# VoltageControl_V1p1.net
KiCad netlist of a schematic drawn in EAGLE
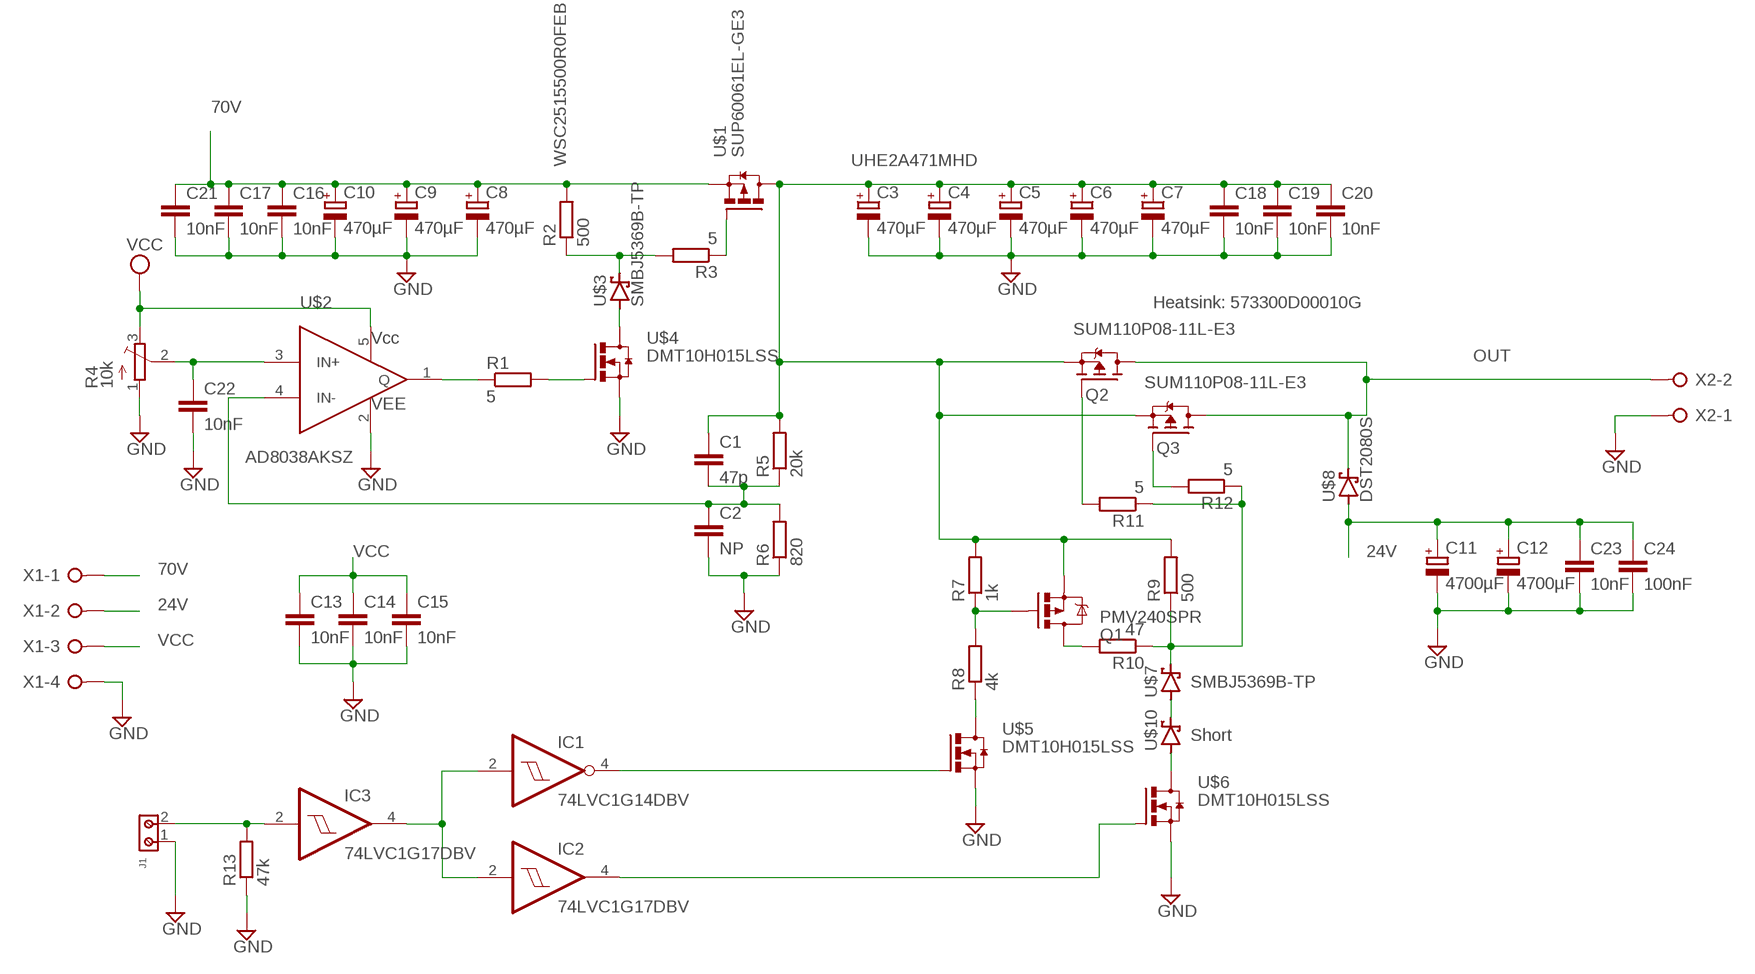
[diagram p0: schematic, sheet 1]

(export (version "E")
  (design (tool "Eeschema 10.0.6"))
  (components
    (comp (ref "C1")
      (value "47p")
      (footprint "eagle-import:C0805")
      (libsource (lib "eagle-import") (part "C-EUC0805"))
    )
    (comp (ref "C2")
      (value "NP")
      (footprint "eagle-import:C0805")
      (libsource (lib "eagle-import") (part "C-EUC0805"))
    )
    (comp (ref "C3")
      (value "470µF")
      (footprint "eagle-import:E7,5-16")
      (libsource (lib "eagle-import") (part "CPOL-EUE7.5-16"))
    )
    (comp (ref "C4")
      (value "470µF")
      (footprint "eagle-import:E7,5-16")
      (libsource (lib "eagle-import") (part "CPOL-EUE7.5-16"))
    )
    (comp (ref "C5")
      (value "470µF")
      (footprint "eagle-import:E7,5-16")
      (libsource (lib "eagle-import") (part "CPOL-EUE7.5-16"))
    )
    (comp (ref "C6")
      (value "470µF")
      (footprint "eagle-import:E7,5-16")
      (libsource (lib "eagle-import") (part "CPOL-EUE7.5-16"))
    )
    (comp (ref "C7")
      (value "470µF")
      (footprint "eagle-import:E7,5-16")
      (libsource (lib "eagle-import") (part "CPOL-EUE7.5-16"))
    )
    (comp (ref "C8")
      (value "470µF")
      (footprint "eagle-import:E7,5-16")
      (libsource (lib "eagle-import") (part "CPOL-EUE7.5-16"))
    )
    (comp (ref "C9")
      (value "470µF")
      (footprint "eagle-import:E7,5-16")
      (libsource (lib "eagle-import") (part "CPOL-EUE7.5-16"))
    )
    (comp (ref "C10")
      (value "470µF")
      (footprint "eagle-import:E7,5-16")
      (libsource (lib "eagle-import") (part "CPOL-EUE7.5-16"))
    )
    (comp (ref "C11")
      (value "4700µF")
      (footprint "eagle-import:E7,5-18")
      (libsource (lib "eagle-import") (part "CPOL-EUE7.5-18"))
    )
    (comp (ref "C12")
      (value "4700µF")
      (footprint "eagle-import:E7,5-18")
      (libsource (lib "eagle-import") (part "CPOL-EUE7.5-18"))
    )
    (comp (ref "C13")
      (value "10nF")
      (footprint "eagle-import:C0805")
      (libsource (lib "eagle-import") (part "C-EUC0805"))
    )
    (comp (ref "C14")
      (value "10nF")
      (footprint "eagle-import:C0805")
      (libsource (lib "eagle-import") (part "C-EUC0805"))
    )
    (comp (ref "C15")
      (value "10nF")
      (footprint "eagle-import:C0805")
      (libsource (lib "eagle-import") (part "C-EUC0805"))
    )
    (comp (ref "C16")
      (value "10nF")
      (footprint "eagle-import:C0805")
      (libsource (lib "eagle-import") (part "C-EUC0805"))
    )
    (comp (ref "C17")
      (value "10nF")
      (footprint "eagle-import:C0805")
      (libsource (lib "eagle-import") (part "C-EUC0805"))
    )
    (comp (ref "C18")
      (value "10nF")
      (footprint "eagle-import:C0805")
      (libsource (lib "eagle-import") (part "C-EUC0805"))
    )
    (comp (ref "C19")
      (value "10nF")
      (footprint "eagle-import:C0805")
      (libsource (lib "eagle-import") (part "C-EUC0805"))
    )
    (comp (ref "C20")
      (value "10nF")
      (footprint "eagle-import:C0805")
      (libsource (lib "eagle-import") (part "C-EUC0805"))
    )
    (comp (ref "C21")
      (value "10nF")
      (footprint "eagle-import:C0805")
      (libsource (lib "eagle-import") (part "C-EUC0805"))
    )
    (comp (ref "C22")
      (value "10nF")
      (footprint "eagle-import:C0805")
      (libsource (lib "eagle-import") (part "C-EUC0805"))
    )
    (comp (ref "C23")
      (value "10nF")
      (footprint "eagle-import:C1206")
      (libsource (lib "eagle-import") (part "C-EUC1206"))
    )
    (comp (ref "C24")
      (value "100nF")
      (footprint "eagle-import:C1206")
      (libsource (lib "eagle-import") (part "C-EUC1206"))
    )
    (comp (ref "IC1")
      (value "74LVC1G14DBV")
      (footprint "eagle-import:SOT23-5")
      (libsource (lib "eagle-import") (part "741G14DBVLVC"))
    )
    (comp (ref "IC2")
      (value "74LVC1G17DBV")
      (footprint "eagle-import:SOT23-5")
      (libsource (lib "eagle-import") (part "741G17DBVLVC"))
    )
    (comp (ref "IC3")
      (value "74LVC1G17DBV")
      (footprint "eagle-import:SOT23-5")
      (libsource (lib "eagle-import") (part "741G17DBVLVC"))
    )
    (comp (ref "J1")
      (value "691210910002")
      (footprint "eagle-import:691210910002")
      (libsource (lib "eagle-import") (part "691210910002"))
    )
    (comp (ref "Q1")
      (value "PMV240SPR")
      (footprint "eagle-import:SOT23-3")
      (libsource (lib "eagle-import") (part "MOSFET-PCHANNEL"))
    )
    (comp (ref "Q2")
      (value "SUM110P08-11L-E3")
      (footprint "eagle-import:TO263")
      (libsource (lib "eagle-import") (part "SPB80P06P"))
    )
    (comp (ref "Q3")
      (value "SUM110P08-11L-E3")
      (footprint "eagle-import:TO263")
      (libsource (lib "eagle-import") (part "SPB80P06P"))
    )
    (comp (ref "R1")
      (value "5")
      (footprint "eagle-import:R0805")
      (libsource (lib "eagle-import") (part "R-EU_R0805"))
    )
    (comp (ref "R2")
      (value "500")
      (footprint "eagle-import:R2512")
      (libsource (lib "eagle-import") (part "R-EU_R2512"))
    )
    (comp (ref "R3")
      (value "5")
      (footprint "eagle-import:R0805")
      (libsource (lib "eagle-import") (part "R-EU_R0805"))
    )
    (comp (ref "R4")
      (value "10k")
      (footprint "eagle-import:SM-42_43X")
      (libsource (lib "eagle-import") (part "TRIM_EU-SM-42/43X"))
    )
    (comp (ref "R5")
      (value "20k")
      (footprint "eagle-import:R0805")
      (libsource (lib "eagle-import") (part "R-EU_R0805"))
    )
    (comp (ref "R6")
      (value "820")
      (footprint "eagle-import:R0805")
      (libsource (lib "eagle-import") (part "R-EU_R0805"))
    )
    (comp (ref "R7")
      (value "1k")
      (footprint "eagle-import:R2512")
      (libsource (lib "eagle-import") (part "R-EU_R2512"))
    )
    (comp (ref "R8")
      (value "4k")
      (footprint "eagle-import:R2512")
      (libsource (lib "eagle-import") (part "R-EU_R2512"))
    )
    (comp (ref "R9")
      (value "500")
      (footprint "eagle-import:R2512")
      (libsource (lib "eagle-import") (part "R-EU_R2512"))
    )
    (comp (ref "R10")
      (value "47")
      (footprint "eagle-import:R0805")
      (libsource (lib "eagle-import") (part "R-EU_R0805"))
    )
    (comp (ref "R11")
      (value "5")
      (footprint "eagle-import:R0805")
      (libsource (lib "eagle-import") (part "R-EU_R0805"))
    )
    (comp (ref "R12")
      (value "5")
      (footprint "eagle-import:R0805")
      (libsource (lib "eagle-import") (part "R-EU_R0805"))
    )
    (comp (ref "R13")
      (value "47k")
      (footprint "eagle-import:R0805")
      (libsource (lib "eagle-import") (part "R-EU_R0805"))
    )
    (comp (ref "U$1")
      (value "SUP60061EL-GE3")
      (footprint "eagle-import:TO220BH")
      (libsource (lib "eagle-import") (part "MOSFET_SUNK"))
    )
    (comp (ref "U$2")
      (value "AD8038AKSZ")
      (footprint "eagle-import:SC70-5")
      (libsource (lib "eagle-import") (part "AD8038AKSZ"))
    )
    (comp (ref "U$3")
      (value "SMBJ5369B-TP")
      (footprint "eagle-import:DO-214AA")
      (libsource (lib "eagle-import") (part "SCHOTTKYDO-214-AA"))
    )
    (comp (ref "U$4")
      (value "DMT10H015LSS")
      (footprint "eagle-import:SOIC8")
      (libsource (lib "eagle-import") (part "DMT10H015LSS"))
    )
    (comp (ref "U$5")
      (value "DMT10H015LSS")
      (footprint "eagle-import:SOIC8")
      (libsource (lib "eagle-import") (part "DMT10H015LSS"))
    )
    (comp (ref "U$6")
      (value "DMT10H015LSS")
      (footprint "eagle-import:SOIC8")
      (libsource (lib "eagle-import") (part "DMT10H015LSS"))
    )
    (comp (ref "U$7")
      (value "SMBJ5369B-TP")
      (footprint "eagle-import:DO-214AA")
      (libsource (lib "eagle-import") (part "SCHOTTKYDO-214-AA"))
    )
    (comp (ref "U$8")
      (value "DST2080S")
      (footprint "eagle-import:TO-277B")
      (libsource (lib "eagle-import") (part "DST2080S"))
    )
    (comp (ref "U$10")
      (value "Short")
      (footprint "eagle-import:DO-214AA")
      (libsource (lib "eagle-import") (part "SCHOTTKYDO-214-AA"))
    )
    (comp (ref "X1")
      (value "W237-04P")
      (footprint "eagle-import:W237-4P")
      (libsource (lib "eagle-import") (part "W237-04P"))
    )
    (comp (ref "X2")
      (value "W237-02P")
      (footprint "eagle-import:W237-132")
      (libsource (lib "eagle-import") (part "W237-02P"))
    )
  )
  (nets
    (net (code "1") (name "/24V") (class "Default")
      (node (ref "C11") (pin "+") (pinfunction "+_+") (pintype "passive"))
      (node (ref "C12") (pin "+") (pinfunction "+_+") (pintype "passive"))
      (node (ref "C23") (pin "1") (pinfunction "1_1") (pintype "passive"))
      (node (ref "C24") (pin "1") (pinfunction "1_1") (pintype "passive"))
      (node (ref "U$8") (pin "P$2") (pinfunction "A_P$2") (pintype "passive"))
      (node (ref "U$8") (pin "P$3") (pinfunction "A_P$3") (pintype "passive"))
      (node (ref "X1") (pin "2") (pinfunction "KL_2") (pintype "passive"))
    )
    (net (code "2") (name "/70V") (class "Default")
      (node (ref "C10") (pin "+") (pinfunction "+_+") (pintype "passive"))
      (node (ref "C16") (pin "1") (pinfunction "1_1") (pintype "passive"))
      (node (ref "C17") (pin "1") (pinfunction "1_1") (pintype "passive"))
      (node (ref "C21") (pin "1") (pinfunction "1_1") (pintype "passive"))
      (node (ref "C8") (pin "+") (pinfunction "+_+") (pintype "passive"))
      (node (ref "C9") (pin "+") (pinfunction "+_+") (pintype "passive"))
      (node (ref "R2") (pin "2") (pinfunction "2_2") (pintype "passive"))
      (node (ref "U$1") (pin "P$3") (pinfunction "S_P$3") (pintype "passive"))
      (node (ref "X1") (pin "1") (pinfunction "KL_1") (pintype "passive"))
    )
    (net (code "3") (name "/OUT") (class "Default")
      (node (ref "Q2") (pin "3") (pinfunction "D_3") (pintype "passive"))
      (node (ref "Q3") (pin "3") (pinfunction "D_3") (pintype "passive"))
      (node (ref "U$8") (pin "P$1") (pinfunction "C_P$1") (pintype "passive"))
      (node (ref "X2") (pin "2") (pinfunction "KL_2") (pintype "passive"))
    )
    (net (code "4") (name "GND") (class "Default")
      (node (ref "C10") (pin "-") (pinfunction "-_-") (pintype "passive"))
      (node (ref "C11") (pin "-") (pinfunction "-_-") (pintype "passive"))
      (node (ref "C12") (pin "-") (pinfunction "-_-") (pintype "passive"))
      (node (ref "C13") (pin "2") (pinfunction "2_2") (pintype "passive"))
      (node (ref "C14") (pin "2") (pinfunction "2_2") (pintype "passive"))
      (node (ref "C15") (pin "2") (pinfunction "2_2") (pintype "passive"))
      (node (ref "C16") (pin "2") (pinfunction "2_2") (pintype "passive"))
      (node (ref "C17") (pin "2") (pinfunction "2_2") (pintype "passive"))
      (node (ref "C18") (pin "2") (pinfunction "2_2") (pintype "passive"))
      (node (ref "C19") (pin "2") (pinfunction "2_2") (pintype "passive"))
      (node (ref "C2") (pin "2") (pinfunction "2_2") (pintype "passive"))
      (node (ref "C20") (pin "2") (pinfunction "2_2") (pintype "passive"))
      (node (ref "C21") (pin "2") (pinfunction "2_2") (pintype "passive"))
      (node (ref "C22") (pin "2") (pinfunction "2_2") (pintype "passive"))
      (node (ref "C23") (pin "2") (pinfunction "2_2") (pintype "passive"))
      (node (ref "C24") (pin "2") (pinfunction "2_2") (pintype "passive"))
      (node (ref "C3") (pin "-") (pinfunction "-_-") (pintype "passive"))
      (node (ref "C4") (pin "-") (pinfunction "-_-") (pintype "passive"))
      (node (ref "C5") (pin "-") (pinfunction "-_-") (pintype "passive"))
      (node (ref "C6") (pin "-") (pinfunction "-_-") (pintype "passive"))
      (node (ref "C7") (pin "-") (pinfunction "-_-") (pintype "passive"))
      (node (ref "C8") (pin "-") (pinfunction "-_-") (pintype "passive"))
      (node (ref "C9") (pin "-") (pinfunction "-_-") (pintype "passive"))
      (node (ref "J1") (pin "1") (pinfunction "1_1") (pintype "passive"))
      (node (ref "R13") (pin "1") (pinfunction "1_1") (pintype "passive"))
      (node (ref "R4") (pin "1") (pinfunction "A_1") (pintype "passive"))
      (node (ref "R6") (pin "1") (pinfunction "1_1") (pintype "passive"))
      (node (ref "U$2") (pin "2") (pinfunction "VEE_2") (pintype "bidirectional"))
      (node (ref "U$4") (pin "1") (pinfunction "S_1") (pintype "passive"))
      (node (ref "U$4") (pin "2") (pinfunction "S_2") (pintype "passive"))
      (node (ref "U$4") (pin "3") (pinfunction "S_3") (pintype "passive"))
      (node (ref "U$5") (pin "1") (pinfunction "S_1") (pintype "passive"))
      (node (ref "U$5") (pin "2") (pinfunction "S_2") (pintype "passive"))
      (node (ref "U$5") (pin "3") (pinfunction "S_3") (pintype "passive"))
      (node (ref "U$6") (pin "1") (pinfunction "S_1") (pintype "passive"))
      (node (ref "U$6") (pin "2") (pinfunction "S_2") (pintype "passive"))
      (node (ref "U$6") (pin "3") (pinfunction "S_3") (pintype "passive"))
      (node (ref "X1") (pin "4") (pinfunction "KL_4") (pintype "passive"))
      (node (ref "X2") (pin "1") (pinfunction "KL_1") (pintype "passive"))
    )
    (net (code "5") (name "Net-(IC1A-I)") (class "Default")
      (node (ref "IC1") (pin "2") (pinfunction "I_2") (pintype "input"))
      (node (ref "IC2") (pin "2") (pinfunction "I_2") (pintype "input"))
      (node (ref "IC3") (pin "4") (pinfunction "O_4") (pintype "output"))
    )
    (net (code "6") (name "Net-(IC1A-O)") (class "Default")
      (node (ref "IC1") (pin "4") (pinfunction "O_4") (pintype "output"))
      (node (ref "U$5") (pin "4") (pinfunction "G_4") (pintype "passive"))
    )
    (net (code "7") (name "Net-(IC2A-O)") (class "Default")
      (node (ref "IC2") (pin "4") (pinfunction "O_4") (pintype "output"))
      (node (ref "U$6") (pin "4") (pinfunction "G_4") (pintype "passive"))
    )
    (net (code "8") (name "Net-(IC3A-I)") (class "Default")
      (node (ref "IC3") (pin "2") (pinfunction "I_2") (pintype "input"))
      (node (ref "J1") (pin "2") (pinfunction "2_2") (pintype "passive"))
      (node (ref "R13") (pin "2") (pinfunction "2_2") (pintype "passive"))
    )
    (net (code "9") (name "Net-(Q1-D)") (class "Default")
      (node (ref "Q1") (pin "3") (pinfunction "D_3") (pintype "passive"))
      (node (ref "R10") (pin "2") (pinfunction "2_2") (pintype "passive"))
    )
    (net (code "10") (name "Net-(Q1-G)") (class "Default")
      (node (ref "Q1") (pin "1") (pinfunction "G_1") (pintype "passive"))
      (node (ref "R7") (pin "1") (pinfunction "1_1") (pintype "passive"))
      (node (ref "R8") (pin "2") (pinfunction "2_2") (pintype "passive"))
    )
    (net (code "11") (name "Net-(Q1-S)") (class "Default")
      (node (ref "C1") (pin "1") (pinfunction "1_1") (pintype "passive"))
      (node (ref "C18") (pin "1") (pinfunction "1_1") (pintype "passive"))
      (node (ref "C19") (pin "1") (pinfunction "1_1") (pintype "passive"))
      (node (ref "C20") (pin "1") (pinfunction "1_1") (pintype "passive"))
      (node (ref "C3") (pin "+") (pinfunction "+_+") (pintype "passive"))
      (node (ref "C4") (pin "+") (pinfunction "+_+") (pintype "passive"))
      (node (ref "C5") (pin "+") (pinfunction "+_+") (pintype "passive"))
      (node (ref "C6") (pin "+") (pinfunction "+_+") (pintype "passive"))
      (node (ref "C7") (pin "+") (pinfunction "+_+") (pintype "passive"))
      (node (ref "Q1") (pin "2") (pinfunction "S_2") (pintype "passive"))
      (node (ref "Q2") (pin "2") (pinfunction "S_2") (pintype "passive"))
      (node (ref "Q3") (pin "2") (pinfunction "S_2") (pintype "passive"))
      (node (ref "R5") (pin "2") (pinfunction "2_2") (pintype "passive"))
      (node (ref "R7") (pin "2") (pinfunction "2_2") (pintype "passive"))
      (node (ref "R9") (pin "2") (pinfunction "2_2") (pintype "passive"))
      (node (ref "U$1") (pin "P$2") (pinfunction "D_P$2") (pintype "passive"))
    )
    (net (code "12") (name "Net-(Q2-G)") (class "Default")
      (node (ref "Q2") (pin "1") (pinfunction "G_1") (pintype "passive"))
      (node (ref "R11") (pin "2") (pinfunction "2_2") (pintype "passive"))
    )
    (net (code "13") (name "Net-(Q3-G)") (class "Default")
      (node (ref "Q3") (pin "1") (pinfunction "G_1") (pintype "passive"))
      (node (ref "R12") (pin "2") (pinfunction "2_2") (pintype "passive"))
    )
    (net (code "14") (name "Net-(R2-Pad1)") (class "Default")
      (node (ref "R2") (pin "1") (pinfunction "1_1") (pintype "passive"))
      (node (ref "R3") (pin "2") (pinfunction "2_2") (pintype "passive"))
      (node (ref "U$3") (pin "C") (pinfunction "C_C") (pintype "passive"))
    )
    (net (code "15") (name "Net-(R4-S)") (class "Default")
      (node (ref "C22") (pin "1") (pinfunction "1_1") (pintype "passive"))
      (node (ref "R4") (pin "2") (pinfunction "S_2") (pintype "passive"))
      (node (ref "U$2") (pin "3") (pinfunction "IN+_3") (pintype "bidirectional"))
    )
    (net (code "16") (name "Net-(R8-Pad1)") (class "Default")
      (node (ref "R8") (pin "1") (pinfunction "1_1") (pintype "passive"))
      (node (ref "U$5") (pin "5") (pinfunction "D_5") (pintype "passive"))
      (node (ref "U$5") (pin "6") (pinfunction "D_6") (pintype "passive"))
      (node (ref "U$5") (pin "7") (pinfunction "D_7") (pintype "passive"))
      (node (ref "U$5") (pin "8") (pinfunction "D_8") (pintype "passive"))
    )
    (net (code "17") (name "Net-(R10-Pad1)") (class "Default")
      (node (ref "R10") (pin "1") (pinfunction "1_1") (pintype "passive"))
      (node (ref "R11") (pin "1") (pinfunction "1_1") (pintype "passive"))
      (node (ref "R12") (pin "1") (pinfunction "1_1") (pintype "passive"))
      (node (ref "R9") (pin "1") (pinfunction "1_1") (pintype "passive"))
      (node (ref "U$7") (pin "C") (pinfunction "C_C") (pintype "passive"))
    )
    (net (code "18") (name "Net-(U$1-G)") (class "Default")
      (node (ref "R3") (pin "1") (pinfunction "1_1") (pintype "passive"))
      (node (ref "U$1") (pin "P$1") (pinfunction "G_P$1") (pintype "passive"))
    )
    (net (code "19") (name "Net-(U$2-IN-)") (class "Default")
      (node (ref "C1") (pin "2") (pinfunction "2_2") (pintype "passive"))
      (node (ref "C2") (pin "1") (pinfunction "1_1") (pintype "passive"))
      (node (ref "R5") (pin "1") (pinfunction "1_1") (pintype "passive"))
      (node (ref "R6") (pin "2") (pinfunction "2_2") (pintype "passive"))
      (node (ref "U$2") (pin "4") (pinfunction "IN-_4") (pintype "bidirectional"))
    )
    (net (code "20") (name "Net-(U$2-Q)") (class "Default")
      (node (ref "R1") (pin "1") (pinfunction "1_1") (pintype "passive"))
      (node (ref "U$2") (pin "1") (pinfunction "Q_1") (pintype "bidirectional"))
    )
    (net (code "21") (name "Net-(U$3-PadA)") (class "Default")
      (node (ref "U$3") (pin "A") (pinfunction "A_A") (pintype "passive"))
      (node (ref "U$4") (pin "5") (pinfunction "D_5") (pintype "passive"))
      (node (ref "U$4") (pin "6") (pinfunction "D_6") (pintype "passive"))
      (node (ref "U$4") (pin "7") (pinfunction "D_7") (pintype "passive"))
      (node (ref "U$4") (pin "8") (pinfunction "D_8") (pintype "passive"))
    )
    (net (code "22") (name "Net-(U$4-G)") (class "Default")
      (node (ref "R1") (pin "2") (pinfunction "2_2") (pintype "passive"))
      (node (ref "U$4") (pin "4") (pinfunction "G_4") (pintype "passive"))
    )
    (net (code "23") (name "Net-(U$10-PadA)") (class "Default")
      (node (ref "U$10") (pin "A") (pinfunction "A_A") (pintype "passive"))
      (node (ref "U$6") (pin "5") (pinfunction "D_5") (pintype "passive"))
      (node (ref "U$6") (pin "6") (pinfunction "D_6") (pintype "passive"))
      (node (ref "U$6") (pin "7") (pinfunction "D_7") (pintype "passive"))
      (node (ref "U$6") (pin "8") (pinfunction "D_8") (pintype "passive"))
    )
    (net (code "24") (name "Net-(U$10-PadC)") (class "Default")
      (node (ref "U$10") (pin "C") (pinfunction "C_C") (pintype "passive"))
      (node (ref "U$7") (pin "A") (pinfunction "A_A") (pintype "passive"))
    )
    (net (code "25") (name "VCC") (class "Default")
      (node (ref "C13") (pin "1") (pinfunction "1_1") (pintype "passive"))
      (node (ref "C14") (pin "1") (pinfunction "1_1") (pintype "passive"))
      (node (ref "C15") (pin "1") (pinfunction "1_1") (pintype "passive"))
      (node (ref "R4") (pin "3") (pinfunction "E_3") (pintype "passive"))
      (node (ref "U$2") (pin "5") (pinfunction "VCC_5") (pintype "bidirectional"))
      (node (ref "X1") (pin "3") (pinfunction "KL_3") (pintype "passive"))
    )
  )
)
